# full_shift_register.net
KiCad netlist of a schematic drawn in EAGLE
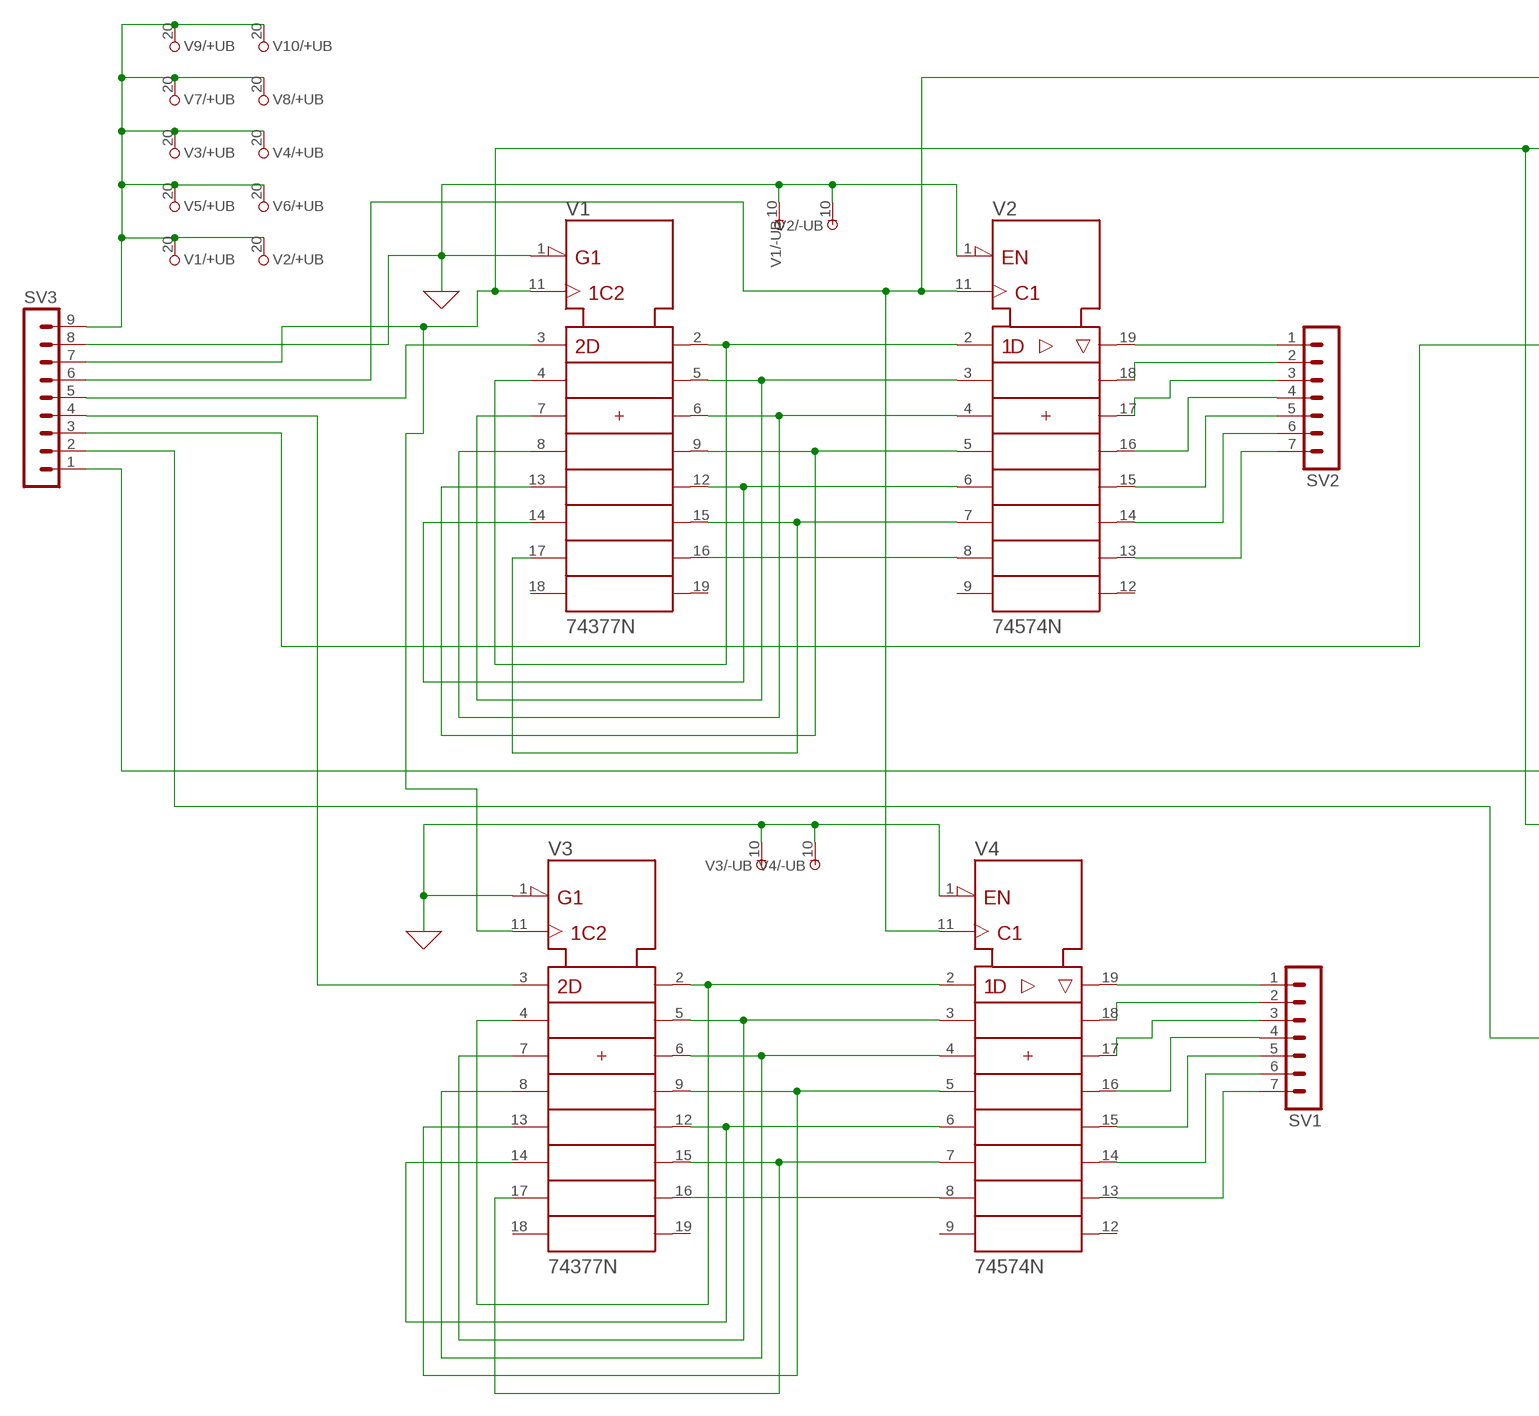
[diagram p0: schematic, sheet 1, part 1 of 2]
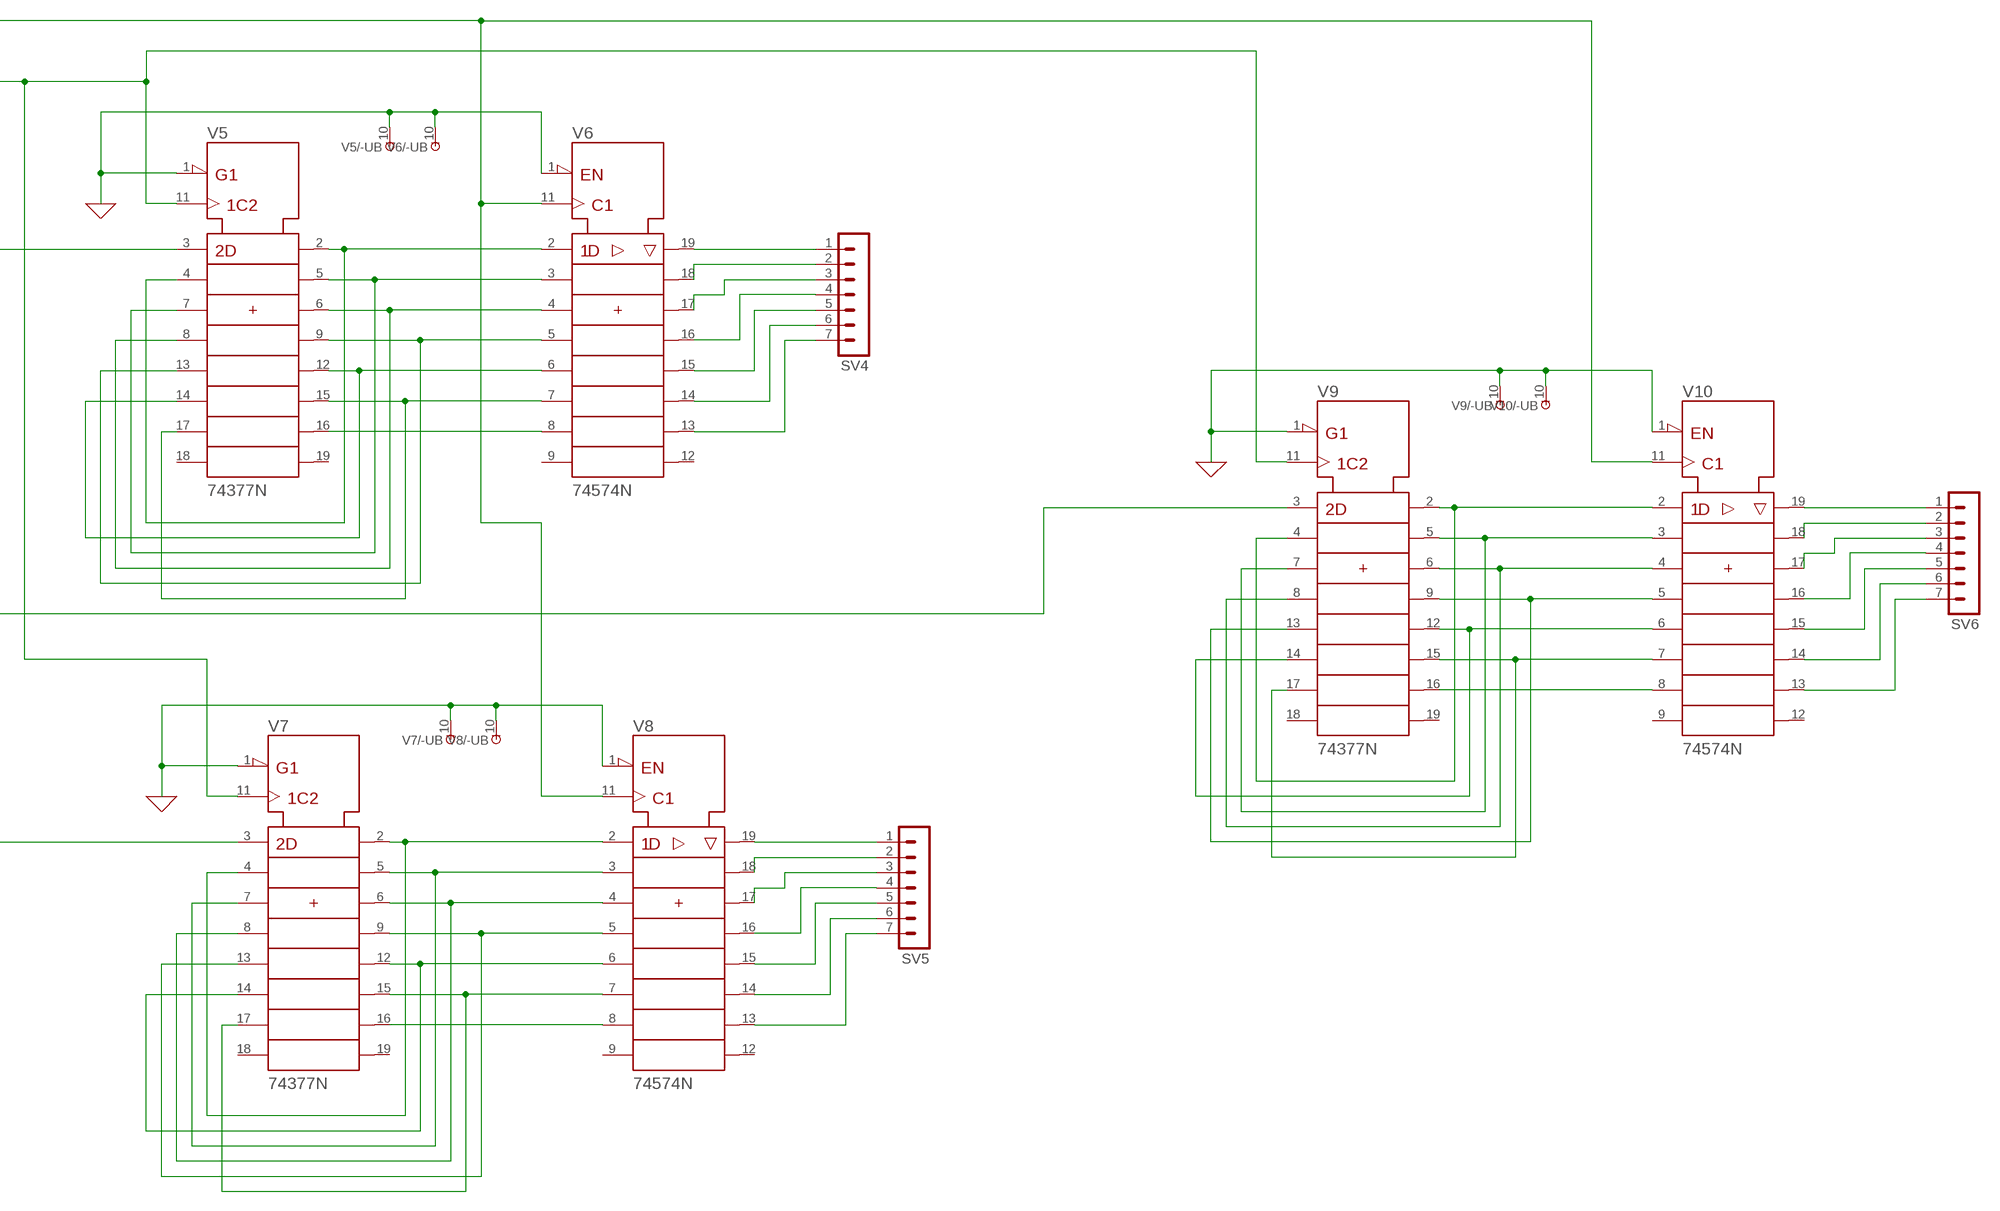
[diagram p1: schematic, sheet 1, part 2 of 2]

(export (version "E")
  (design (tool "Eeschema 10.0.6"))
  (components
    (comp (ref "SV1")
      (value "MA07-1")
      (footprint "eagle-import:MA07-1")
      (libsource (lib "eagle-import") (part "MA07-1"))
    )
    (comp (ref "SV2")
      (value "MA07-1")
      (footprint "eagle-import:MA07-1")
      (libsource (lib "eagle-import") (part "MA07-1"))
    )
    (comp (ref "SV3")
      (value "MA09-1")
      (footprint "eagle-import:MA09-1")
      (libsource (lib "eagle-import") (part "MA09-1"))
    )
    (comp (ref "SV4")
      (value "MA07-1")
      (footprint "eagle-import:MA07-1")
      (libsource (lib "eagle-import") (part "MA07-1"))
    )
    (comp (ref "SV5")
      (value "MA07-1")
      (footprint "eagle-import:MA07-1")
      (libsource (lib "eagle-import") (part "MA07-1"))
    )
    (comp (ref "SV6")
      (value "MA07-1")
      (footprint "eagle-import:MA07-1")
      (libsource (lib "eagle-import") (part "MA07-1"))
    )
    (comp (ref "V1")
      (value "74377N")
      (footprint "eagle-import:DIL20")
      (libsource (lib "eagle-import") (part "74377N"))
    )
    (comp (ref "V2")
      (value "74574N")
      (footprint "eagle-import:DIL20")
      (libsource (lib "eagle-import") (part "74574N"))
    )
    (comp (ref "V3")
      (value "74377N")
      (footprint "eagle-import:DIL20")
      (libsource (lib "eagle-import") (part "74377N"))
    )
    (comp (ref "V4")
      (value "74574N")
      (footprint "eagle-import:DIL20")
      (libsource (lib "eagle-import") (part "74574N"))
    )
    (comp (ref "V5")
      (value "74377N")
      (footprint "eagle-import:DIL20")
      (libsource (lib "eagle-import") (part "74377N"))
    )
    (comp (ref "V6")
      (value "74574N")
      (footprint "eagle-import:DIL20")
      (libsource (lib "eagle-import") (part "74574N"))
    )
    (comp (ref "V7")
      (value "74377N")
      (footprint "eagle-import:DIL20")
      (libsource (lib "eagle-import") (part "74377N"))
    )
    (comp (ref "V8")
      (value "74574N")
      (footprint "eagle-import:DIL20")
      (libsource (lib "eagle-import") (part "74574N"))
    )
    (comp (ref "V9")
      (value "74377N")
      (footprint "eagle-import:DIL20")
      (libsource (lib "eagle-import") (part "74377N"))
    )
    (comp (ref "V10")
      (value "74574N")
      (footprint "eagle-import:DIL20")
      (libsource (lib "eagle-import") (part "74574N"))
    )
  )
  (nets
    (net (code "1") (name "GND") (class "Default")
      (node (ref "SV3") (pin "8") (pinfunction "8_8") (pintype "passive"))
      (node (ref "V1") (pin "1") (pinfunction "~{G}_1") (pintype "input"))
      (node (ref "V1") (pin "10") (pinfunction "-UB_10") (pintype "power_in"))
      (node (ref "V10") (pin "1") (pinfunction "~{OC}_1") (pintype "input"))
      (node (ref "V10") (pin "10") (pinfunction "-UB_10") (pintype "power_in"))
      (node (ref "V2") (pin "1") (pinfunction "~{OC}_1") (pintype "input"))
      (node (ref "V2") (pin "10") (pinfunction "-UB_10") (pintype "power_in"))
      (node (ref "V3") (pin "1") (pinfunction "~{G}_1") (pintype "input"))
      (node (ref "V3") (pin "10") (pinfunction "-UB_10") (pintype "power_in"))
      (node (ref "V4") (pin "1") (pinfunction "~{OC}_1") (pintype "input"))
      (node (ref "V4") (pin "10") (pinfunction "-UB_10") (pintype "power_in"))
      (node (ref "V5") (pin "1") (pinfunction "~{G}_1") (pintype "input"))
      (node (ref "V5") (pin "10") (pinfunction "-UB_10") (pintype "power_in"))
      (node (ref "V6") (pin "1") (pinfunction "~{OC}_1") (pintype "input"))
      (node (ref "V6") (pin "10") (pinfunction "-UB_10") (pintype "power_in"))
      (node (ref "V7") (pin "1") (pinfunction "~{G}_1") (pintype "input"))
      (node (ref "V7") (pin "10") (pinfunction "-UB_10") (pintype "power_in"))
      (node (ref "V8") (pin "1") (pinfunction "~{OC}_1") (pintype "input"))
      (node (ref "V8") (pin "10") (pinfunction "-UB_10") (pintype "power_in"))
      (node (ref "V9") (pin "1") (pinfunction "~{G}_1") (pintype "input"))
      (node (ref "V9") (pin "10") (pinfunction "-UB_10") (pintype "power_in"))
    )
    (net (code "2") (name "Net-(V1C-1D)") (class "Default")
      (node (ref "SV3") (pin "5") (pinfunction "5_5") (pintype "passive"))
      (node (ref "V1") (pin "3") (pinfunction "1D_3") (pintype "input"))
    )
    (net (code "3") (name "Net-(V1C-1Q)") (class "Default")
      (node (ref "V1") (pin "2") (pinfunction "1Q_2") (pintype "output"))
      (node (ref "V1") (pin "4") (pinfunction "2D_4") (pintype "input"))
      (node (ref "V2") (pin "2") (pinfunction "1D_2") (pintype "input"))
    )
    (net (code "4") (name "Net-(V1C-2Q)") (class "Default")
      (node (ref "V1") (pin "5") (pinfunction "2Q_5") (pintype "output"))
      (node (ref "V1") (pin "7") (pinfunction "3D_7") (pintype "input"))
      (node (ref "V2") (pin "3") (pinfunction "2D_3") (pintype "input"))
    )
    (net (code "5") (name "Net-(V1C-3Q)") (class "Default")
      (node (ref "V1") (pin "6") (pinfunction "3Q_6") (pintype "output"))
      (node (ref "V1") (pin "8") (pinfunction "4D_8") (pintype "input"))
      (node (ref "V2") (pin "4") (pinfunction "3D_4") (pintype "input"))
    )
    (net (code "6") (name "Net-(V1C-4Q)") (class "Default")
      (node (ref "V1") (pin "13") (pinfunction "5D_13") (pintype "input"))
      (node (ref "V1") (pin "9") (pinfunction "4Q_9") (pintype "output"))
      (node (ref "V2") (pin "5") (pinfunction "4D_5") (pintype "input"))
    )
    (net (code "7") (name "Net-(V1C-5Q)") (class "Default")
      (node (ref "V1") (pin "12") (pinfunction "5Q_12") (pintype "output"))
      (node (ref "V1") (pin "14") (pinfunction "6D_14") (pintype "input"))
      (node (ref "V2") (pin "6") (pinfunction "5D_6") (pintype "input"))
    )
    (net (code "8") (name "Net-(V1C-6Q)") (class "Default")
      (node (ref "V1") (pin "15") (pinfunction "6Q_15") (pintype "output"))
      (node (ref "V1") (pin "17") (pinfunction "7D_17") (pintype "input"))
      (node (ref "V2") (pin "7") (pinfunction "6D_7") (pintype "input"))
    )
    (net (code "9") (name "Net-(V1C-7Q)") (class "Default")
      (node (ref "V1") (pin "16") (pinfunction "7Q_16") (pintype "output"))
      (node (ref "V2") (pin "8") (pinfunction "7D_8") (pintype "input"))
    )
    (net (code "10") (name "Net-(V1C-CLK)") (class "Default")
      (node (ref "SV3") (pin "7") (pinfunction "7_7") (pintype "passive"))
      (node (ref "V1") (pin "11") (pinfunction "CLK_11") (pintype "input"))
      (node (ref "V3") (pin "11") (pinfunction "CLK_11") (pintype "input"))
      (node (ref "V5") (pin "11") (pinfunction "CLK_11") (pintype "input"))
      (node (ref "V7") (pin "11") (pinfunction "CLK_11") (pintype "input"))
      (node (ref "V9") (pin "11") (pinfunction "CLK_11") (pintype "input"))
    )
    (net (code "11") (name "Net-(V2C-1Q)") (class "Default")
      (node (ref "SV2") (pin "1") (pinfunction "1_1") (pintype "passive"))
      (node (ref "V2") (pin "19") (pinfunction "1Q_19") (pintype "tri_state"))
    )
    (net (code "12") (name "Net-(V2C-2Q)") (class "Default")
      (node (ref "SV2") (pin "2") (pinfunction "2_2") (pintype "passive"))
      (node (ref "V2") (pin "18") (pinfunction "2Q_18") (pintype "tri_state"))
    )
    (net (code "13") (name "Net-(V2C-3Q)") (class "Default")
      (node (ref "SV2") (pin "3") (pinfunction "3_3") (pintype "passive"))
      (node (ref "V2") (pin "17") (pinfunction "3Q_17") (pintype "tri_state"))
    )
    (net (code "14") (name "Net-(V2C-4Q)") (class "Default")
      (node (ref "SV2") (pin "4") (pinfunction "4_4") (pintype "passive"))
      (node (ref "V2") (pin "16") (pinfunction "4Q_16") (pintype "tri_state"))
    )
    (net (code "15") (name "Net-(V2C-5Q)") (class "Default")
      (node (ref "SV2") (pin "5") (pinfunction "5_5") (pintype "passive"))
      (node (ref "V2") (pin "15") (pinfunction "5Q_15") (pintype "tri_state"))
    )
    (net (code "16") (name "Net-(V2C-6Q)") (class "Default")
      (node (ref "SV2") (pin "6") (pinfunction "6_6") (pintype "passive"))
      (node (ref "V2") (pin "14") (pinfunction "6Q_14") (pintype "tri_state"))
    )
    (net (code "17") (name "Net-(V2C-7Q)") (class "Default")
      (node (ref "SV2") (pin "7") (pinfunction "7_7") (pintype "passive"))
      (node (ref "V2") (pin "13") (pinfunction "7Q_13") (pintype "tri_state"))
    )
    (net (code "18") (name "Net-(V3C-1D)") (class "Default")
      (node (ref "SV3") (pin "4") (pinfunction "4_4") (pintype "passive"))
      (node (ref "V3") (pin "3") (pinfunction "1D_3") (pintype "input"))
    )
    (net (code "19") (name "Net-(V3C-1Q)") (class "Default")
      (node (ref "V3") (pin "2") (pinfunction "1Q_2") (pintype "output"))
      (node (ref "V3") (pin "4") (pinfunction "2D_4") (pintype "input"))
      (node (ref "V4") (pin "2") (pinfunction "1D_2") (pintype "input"))
    )
    (net (code "20") (name "Net-(V3C-2Q)") (class "Default")
      (node (ref "V3") (pin "5") (pinfunction "2Q_5") (pintype "output"))
      (node (ref "V3") (pin "7") (pinfunction "3D_7") (pintype "input"))
      (node (ref "V4") (pin "3") (pinfunction "2D_3") (pintype "input"))
    )
    (net (code "21") (name "Net-(V3C-3Q)") (class "Default")
      (node (ref "V3") (pin "6") (pinfunction "3Q_6") (pintype "output"))
      (node (ref "V3") (pin "8") (pinfunction "4D_8") (pintype "input"))
      (node (ref "V4") (pin "4") (pinfunction "3D_4") (pintype "input"))
    )
    (net (code "22") (name "Net-(V3C-4Q)") (class "Default")
      (node (ref "V3") (pin "13") (pinfunction "5D_13") (pintype "input"))
      (node (ref "V3") (pin "9") (pinfunction "4Q_9") (pintype "output"))
      (node (ref "V4") (pin "5") (pinfunction "4D_5") (pintype "input"))
    )
    (net (code "23") (name "Net-(V3C-5Q)") (class "Default")
      (node (ref "V3") (pin "12") (pinfunction "5Q_12") (pintype "output"))
      (node (ref "V3") (pin "14") (pinfunction "6D_14") (pintype "input"))
      (node (ref "V4") (pin "6") (pinfunction "5D_6") (pintype "input"))
    )
    (net (code "24") (name "Net-(V3C-6Q)") (class "Default")
      (node (ref "V3") (pin "15") (pinfunction "6Q_15") (pintype "output"))
      (node (ref "V3") (pin "17") (pinfunction "7D_17") (pintype "input"))
      (node (ref "V4") (pin "7") (pinfunction "6D_7") (pintype "input"))
    )
    (net (code "25") (name "Net-(V3C-7Q)") (class "Default")
      (node (ref "V3") (pin "16") (pinfunction "7Q_16") (pintype "output"))
      (node (ref "V4") (pin "8") (pinfunction "7D_8") (pintype "input"))
    )
    (net (code "26") (name "Net-(V4C-1Q)") (class "Default")
      (node (ref "SV1") (pin "1") (pinfunction "1_1") (pintype "passive"))
      (node (ref "V4") (pin "19") (pinfunction "1Q_19") (pintype "tri_state"))
    )
    (net (code "27") (name "Net-(V4C-2Q)") (class "Default")
      (node (ref "SV1") (pin "2") (pinfunction "2_2") (pintype "passive"))
      (node (ref "V4") (pin "18") (pinfunction "2Q_18") (pintype "tri_state"))
    )
    (net (code "28") (name "Net-(V4C-3Q)") (class "Default")
      (node (ref "SV1") (pin "3") (pinfunction "3_3") (pintype "passive"))
      (node (ref "V4") (pin "17") (pinfunction "3Q_17") (pintype "tri_state"))
    )
    (net (code "29") (name "Net-(V4C-4Q)") (class "Default")
      (node (ref "SV1") (pin "4") (pinfunction "4_4") (pintype "passive"))
      (node (ref "V4") (pin "16") (pinfunction "4Q_16") (pintype "tri_state"))
    )
    (net (code "30") (name "Net-(V4C-5Q)") (class "Default")
      (node (ref "SV1") (pin "5") (pinfunction "5_5") (pintype "passive"))
      (node (ref "V4") (pin "15") (pinfunction "5Q_15") (pintype "tri_state"))
    )
    (net (code "31") (name "Net-(V4C-6Q)") (class "Default")
      (node (ref "SV1") (pin "6") (pinfunction "6_6") (pintype "passive"))
      (node (ref "V4") (pin "14") (pinfunction "6Q_14") (pintype "tri_state"))
    )
    (net (code "32") (name "Net-(V4C-7Q)") (class "Default")
      (node (ref "SV1") (pin "7") (pinfunction "7_7") (pintype "passive"))
      (node (ref "V4") (pin "13") (pinfunction "7Q_13") (pintype "tri_state"))
    )
    (net (code "33") (name "Net-(V5C-1D)") (class "Default")
      (node (ref "SV3") (pin "3") (pinfunction "3_3") (pintype "passive"))
      (node (ref "V5") (pin "3") (pinfunction "1D_3") (pintype "input"))
    )
    (net (code "34") (name "Net-(V5C-1Q)") (class "Default")
      (node (ref "V5") (pin "2") (pinfunction "1Q_2") (pintype "output"))
      (node (ref "V5") (pin "4") (pinfunction "2D_4") (pintype "input"))
      (node (ref "V6") (pin "2") (pinfunction "1D_2") (pintype "input"))
    )
    (net (code "35") (name "Net-(V5C-2Q)") (class "Default")
      (node (ref "V5") (pin "5") (pinfunction "2Q_5") (pintype "output"))
      (node (ref "V5") (pin "7") (pinfunction "3D_7") (pintype "input"))
      (node (ref "V6") (pin "3") (pinfunction "2D_3") (pintype "input"))
    )
    (net (code "36") (name "Net-(V5C-3Q)") (class "Default")
      (node (ref "V5") (pin "6") (pinfunction "3Q_6") (pintype "output"))
      (node (ref "V5") (pin "8") (pinfunction "4D_8") (pintype "input"))
      (node (ref "V6") (pin "4") (pinfunction "3D_4") (pintype "input"))
    )
    (net (code "37") (name "Net-(V5C-4Q)") (class "Default")
      (node (ref "V5") (pin "13") (pinfunction "5D_13") (pintype "input"))
      (node (ref "V5") (pin "9") (pinfunction "4Q_9") (pintype "output"))
      (node (ref "V6") (pin "5") (pinfunction "4D_5") (pintype "input"))
    )
    (net (code "38") (name "Net-(V5C-5Q)") (class "Default")
      (node (ref "V5") (pin "12") (pinfunction "5Q_12") (pintype "output"))
      (node (ref "V5") (pin "14") (pinfunction "6D_14") (pintype "input"))
      (node (ref "V6") (pin "6") (pinfunction "5D_6") (pintype "input"))
    )
    (net (code "39") (name "Net-(V5C-6Q)") (class "Default")
      (node (ref "V5") (pin "15") (pinfunction "6Q_15") (pintype "output"))
      (node (ref "V5") (pin "17") (pinfunction "7D_17") (pintype "input"))
      (node (ref "V6") (pin "7") (pinfunction "6D_7") (pintype "input"))
    )
    (net (code "40") (name "Net-(V5C-7Q)") (class "Default")
      (node (ref "V5") (pin "16") (pinfunction "7Q_16") (pintype "output"))
      (node (ref "V6") (pin "8") (pinfunction "7D_8") (pintype "input"))
    )
    (net (code "41") (name "Net-(V6C-1Q)") (class "Default")
      (node (ref "SV4") (pin "1") (pinfunction "1_1") (pintype "passive"))
      (node (ref "V6") (pin "19") (pinfunction "1Q_19") (pintype "tri_state"))
    )
    (net (code "42") (name "Net-(V6C-2Q)") (class "Default")
      (node (ref "SV4") (pin "2") (pinfunction "2_2") (pintype "passive"))
      (node (ref "V6") (pin "18") (pinfunction "2Q_18") (pintype "tri_state"))
    )
    (net (code "43") (name "Net-(V6C-3Q)") (class "Default")
      (node (ref "SV4") (pin "3") (pinfunction "3_3") (pintype "passive"))
      (node (ref "V6") (pin "17") (pinfunction "3Q_17") (pintype "tri_state"))
    )
    (net (code "44") (name "Net-(V6C-4Q)") (class "Default")
      (node (ref "SV4") (pin "4") (pinfunction "4_4") (pintype "passive"))
      (node (ref "V6") (pin "16") (pinfunction "4Q_16") (pintype "tri_state"))
    )
    (net (code "45") (name "Net-(V6C-5Q)") (class "Default")
      (node (ref "SV4") (pin "5") (pinfunction "5_5") (pintype "passive"))
      (node (ref "V6") (pin "15") (pinfunction "5Q_15") (pintype "tri_state"))
    )
    (net (code "46") (name "Net-(V6C-6Q)") (class "Default")
      (node (ref "SV4") (pin "6") (pinfunction "6_6") (pintype "passive"))
      (node (ref "V6") (pin "14") (pinfunction "6Q_14") (pintype "tri_state"))
    )
    (net (code "47") (name "Net-(V6C-7Q)") (class "Default")
      (node (ref "SV4") (pin "7") (pinfunction "7_7") (pintype "passive"))
      (node (ref "V6") (pin "13") (pinfunction "7Q_13") (pintype "tri_state"))
    )
    (net (code "48") (name "Net-(V7C-1D)") (class "Default")
      (node (ref "SV3") (pin "2") (pinfunction "2_2") (pintype "passive"))
      (node (ref "V7") (pin "3") (pinfunction "1D_3") (pintype "input"))
    )
    (net (code "49") (name "Net-(V7C-1Q)") (class "Default")
      (node (ref "V7") (pin "2") (pinfunction "1Q_2") (pintype "output"))
      (node (ref "V7") (pin "4") (pinfunction "2D_4") (pintype "input"))
      (node (ref "V8") (pin "2") (pinfunction "1D_2") (pintype "input"))
    )
    (net (code "50") (name "Net-(V7C-2Q)") (class "Default")
      (node (ref "V7") (pin "5") (pinfunction "2Q_5") (pintype "output"))
      (node (ref "V7") (pin "7") (pinfunction "3D_7") (pintype "input"))
      (node (ref "V8") (pin "3") (pinfunction "2D_3") (pintype "input"))
    )
    (net (code "51") (name "Net-(V7C-3Q)") (class "Default")
      (node (ref "V7") (pin "6") (pinfunction "3Q_6") (pintype "output"))
      (node (ref "V7") (pin "8") (pinfunction "4D_8") (pintype "input"))
      (node (ref "V8") (pin "4") (pinfunction "3D_4") (pintype "input"))
    )
    (net (code "52") (name "Net-(V7C-4Q)") (class "Default")
      (node (ref "V7") (pin "13") (pinfunction "5D_13") (pintype "input"))
      (node (ref "V7") (pin "9") (pinfunction "4Q_9") (pintype "output"))
      (node (ref "V8") (pin "5") (pinfunction "4D_5") (pintype "input"))
    )
    (net (code "53") (name "Net-(V7C-5Q)") (class "Default")
      (node (ref "V7") (pin "12") (pinfunction "5Q_12") (pintype "output"))
      (node (ref "V7") (pin "14") (pinfunction "6D_14") (pintype "input"))
      (node (ref "V8") (pin "6") (pinfunction "5D_6") (pintype "input"))
    )
    (net (code "54") (name "Net-(V7C-6Q)") (class "Default")
      (node (ref "V7") (pin "15") (pinfunction "6Q_15") (pintype "output"))
      (node (ref "V7") (pin "17") (pinfunction "7D_17") (pintype "input"))
      (node (ref "V8") (pin "7") (pinfunction "6D_7") (pintype "input"))
    )
    (net (code "55") (name "Net-(V7C-7Q)") (class "Default")
      (node (ref "V7") (pin "16") (pinfunction "7Q_16") (pintype "output"))
      (node (ref "V8") (pin "8") (pinfunction "7D_8") (pintype "input"))
    )
    (net (code "56") (name "Net-(V8C-1Q)") (class "Default")
      (node (ref "SV5") (pin "1") (pinfunction "1_1") (pintype "passive"))
      (node (ref "V8") (pin "19") (pinfunction "1Q_19") (pintype "tri_state"))
    )
    (net (code "57") (name "Net-(V8C-2Q)") (class "Default")
      (node (ref "SV5") (pin "2") (pinfunction "2_2") (pintype "passive"))
      (node (ref "V8") (pin "18") (pinfunction "2Q_18") (pintype "tri_state"))
    )
    (net (code "58") (name "Net-(V8C-3Q)") (class "Default")
      (node (ref "SV5") (pin "3") (pinfunction "3_3") (pintype "passive"))
      (node (ref "V8") (pin "17") (pinfunction "3Q_17") (pintype "tri_state"))
    )
    (net (code "59") (name "Net-(V8C-4Q)") (class "Default")
      (node (ref "SV5") (pin "4") (pinfunction "4_4") (pintype "passive"))
      (node (ref "V8") (pin "16") (pinfunction "4Q_16") (pintype "tri_state"))
    )
    (net (code "60") (name "Net-(V8C-5Q)") (class "Default")
      (node (ref "SV5") (pin "5") (pinfunction "5_5") (pintype "passive"))
      (node (ref "V8") (pin "15") (pinfunction "5Q_15") (pintype "tri_state"))
    )
    (net (code "61") (name "Net-(V8C-6Q)") (class "Default")
      (node (ref "SV5") (pin "6") (pinfunction "6_6") (pintype "passive"))
      (node (ref "V8") (pin "14") (pinfunction "6Q_14") (pintype "tri_state"))
    )
    (net (code "62") (name "Net-(V8C-7Q)") (class "Default")
      (node (ref "SV5") (pin "7") (pinfunction "7_7") (pintype "passive"))
      (node (ref "V8") (pin "13") (pinfunction "7Q_13") (pintype "tri_state"))
    )
    (net (code "63") (name "Net-(V9C-1D)") (class "Default")
      (node (ref "SV3") (pin "1") (pinfunction "1_1") (pintype "passive"))
      (node (ref "V9") (pin "3") (pinfunction "1D_3") (pintype "input"))
    )
    (net (code "64") (name "Net-(V10A-+UB)") (class "Default")
      (node (ref "SV3") (pin "9") (pinfunction "9_9") (pintype "passive"))
      (node (ref "V1") (pin "20") (pinfunction "+UB_20") (pintype "power_in"))
      (node (ref "V10") (pin "20") (pinfunction "+UB_20") (pintype "power_in"))
      (node (ref "V2") (pin "20") (pinfunction "+UB_20") (pintype "power_in"))
      (node (ref "V3") (pin "20") (pinfunction "+UB_20") (pintype "power_in"))
      (node (ref "V4") (pin "20") (pinfunction "+UB_20") (pintype "power_in"))
      (node (ref "V5") (pin "20") (pinfunction "+UB_20") (pintype "power_in"))
      (node (ref "V6") (pin "20") (pinfunction "+UB_20") (pintype "power_in"))
      (node (ref "V7") (pin "20") (pinfunction "+UB_20") (pintype "power_in"))
      (node (ref "V8") (pin "20") (pinfunction "+UB_20") (pintype "power_in"))
      (node (ref "V9") (pin "20") (pinfunction "+UB_20") (pintype "power_in"))
    )
    (net (code "65") (name "Net-(V10C-1D)") (class "Default")
      (node (ref "V10") (pin "2") (pinfunction "1D_2") (pintype "input"))
      (node (ref "V9") (pin "2") (pinfunction "1Q_2") (pintype "output"))
      (node (ref "V9") (pin "4") (pinfunction "2D_4") (pintype "input"))
    )
    (net (code "66") (name "Net-(V10C-1Q)") (class "Default")
      (node (ref "SV6") (pin "1") (pinfunction "1_1") (pintype "passive"))
      (node (ref "V10") (pin "19") (pinfunction "1Q_19") (pintype "tri_state"))
    )
    (net (code "67") (name "Net-(V10C-2D)") (class "Default")
      (node (ref "V10") (pin "3") (pinfunction "2D_3") (pintype "input"))
      (node (ref "V9") (pin "5") (pinfunction "2Q_5") (pintype "output"))
      (node (ref "V9") (pin "7") (pinfunction "3D_7") (pintype "input"))
    )
    (net (code "68") (name "Net-(V10C-2Q)") (class "Default")
      (node (ref "SV6") (pin "2") (pinfunction "2_2") (pintype "passive"))
      (node (ref "V10") (pin "18") (pinfunction "2Q_18") (pintype "tri_state"))
    )
    (net (code "69") (name "Net-(V10C-3D)") (class "Default")
      (node (ref "V10") (pin "4") (pinfunction "3D_4") (pintype "input"))
      (node (ref "V9") (pin "6") (pinfunction "3Q_6") (pintype "output"))
      (node (ref "V9") (pin "8") (pinfunction "4D_8") (pintype "input"))
    )
    (net (code "70") (name "Net-(V10C-3Q)") (class "Default")
      (node (ref "SV6") (pin "3") (pinfunction "3_3") (pintype "passive"))
      (node (ref "V10") (pin "17") (pinfunction "3Q_17") (pintype "tri_state"))
    )
    (net (code "71") (name "Net-(V10C-4D)") (class "Default")
      (node (ref "V10") (pin "5") (pinfunction "4D_5") (pintype "input"))
      (node (ref "V9") (pin "13") (pinfunction "5D_13") (pintype "input"))
      (node (ref "V9") (pin "9") (pinfunction "4Q_9") (pintype "output"))
    )
    (net (code "72") (name "Net-(V10C-4Q)") (class "Default")
      (node (ref "SV6") (pin "4") (pinfunction "4_4") (pintype "passive"))
      (node (ref "V10") (pin "16") (pinfunction "4Q_16") (pintype "tri_state"))
    )
    (net (code "73") (name "Net-(V10C-5D)") (class "Default")
      (node (ref "V10") (pin "6") (pinfunction "5D_6") (pintype "input"))
      (node (ref "V9") (pin "12") (pinfunction "5Q_12") (pintype "output"))
      (node (ref "V9") (pin "14") (pinfunction "6D_14") (pintype "input"))
    )
    (net (code "74") (name "Net-(V10C-5Q)") (class "Default")
      (node (ref "SV6") (pin "5") (pinfunction "5_5") (pintype "passive"))
      (node (ref "V10") (pin "15") (pinfunction "5Q_15") (pintype "tri_state"))
    )
    (net (code "75") (name "Net-(V10C-6D)") (class "Default")
      (node (ref "V10") (pin "7") (pinfunction "6D_7") (pintype "input"))
      (node (ref "V9") (pin "15") (pinfunction "6Q_15") (pintype "output"))
      (node (ref "V9") (pin "17") (pinfunction "7D_17") (pintype "input"))
    )
    (net (code "76") (name "Net-(V10C-6Q)") (class "Default")
      (node (ref "SV6") (pin "6") (pinfunction "6_6") (pintype "passive"))
      (node (ref "V10") (pin "14") (pinfunction "6Q_14") (pintype "tri_state"))
    )
    (net (code "77") (name "Net-(V10C-7D)") (class "Default")
      (node (ref "V10") (pin "8") (pinfunction "7D_8") (pintype "input"))
      (node (ref "V9") (pin "16") (pinfunction "7Q_16") (pintype "output"))
    )
    (net (code "78") (name "Net-(V10C-7Q)") (class "Default")
      (node (ref "SV6") (pin "7") (pinfunction "7_7") (pintype "passive"))
      (node (ref "V10") (pin "13") (pinfunction "7Q_13") (pintype "tri_state"))
    )
    (net (code "79") (name "Net-(V10C-CLK)") (class "Default")
      (node (ref "SV3") (pin "6") (pinfunction "6_6") (pintype "passive"))
      (node (ref "V10") (pin "11") (pinfunction "CLK_11") (pintype "input"))
      (node (ref "V2") (pin "11") (pinfunction "CLK_11") (pintype "input"))
      (node (ref "V4") (pin "11") (pinfunction "CLK_11") (pintype "input"))
      (node (ref "V6") (pin "11") (pinfunction "CLK_11") (pintype "input"))
      (node (ref "V8") (pin "11") (pinfunction "CLK_11") (pintype "input"))
    )
    (net (code "80") (name "unconnected-(V1C-8D-Pad18)") (class "Default")
      (node (ref "V1") (pin "18") (pinfunction "8D_18") (pintype "input"))
    )
    (net (code "81") (name "unconnected-(V1C-8Q-Pad19)") (class "Default")
      (node (ref "V1") (pin "19") (pinfunction "8Q_19") (pintype "output"))
    )
    (net (code "82") (name "unconnected-(V2C-8D-Pad9)") (class "Default")
      (node (ref "V2") (pin "9") (pinfunction "8D_9") (pintype "input"))
    )
    (net (code "83") (name "unconnected-(V2C-8Q-Pad12)") (class "Default")
      (node (ref "V2") (pin "12") (pinfunction "8Q_12") (pintype "tri_state"))
    )
    (net (code "84") (name "unconnected-(V3C-8D-Pad18)") (class "Default")
      (node (ref "V3") (pin "18") (pinfunction "8D_18") (pintype "input"))
    )
    (net (code "85") (name "unconnected-(V3C-8Q-Pad19)") (class "Default")
      (node (ref "V3") (pin "19") (pinfunction "8Q_19") (pintype "output"))
    )
    (net (code "86") (name "unconnected-(V4C-8D-Pad9)") (class "Default")
      (node (ref "V4") (pin "9") (pinfunction "8D_9") (pintype "input"))
    )
    (net (code "87") (name "unconnected-(V4C-8Q-Pad12)") (class "Default")
      (node (ref "V4") (pin "12") (pinfunction "8Q_12") (pintype "tri_state"))
    )
    (net (code "88") (name "unconnected-(V5C-8D-Pad18)") (class "Default")
      (node (ref "V5") (pin "18") (pinfunction "8D_18") (pintype "input"))
    )
    (net (code "89") (name "unconnected-(V5C-8Q-Pad19)") (class "Default")
      (node (ref "V5") (pin "19") (pinfunction "8Q_19") (pintype "output"))
    )
    (net (code "90") (name "unconnected-(V6C-8D-Pad9)") (class "Default")
      (node (ref "V6") (pin "9") (pinfunction "8D_9") (pintype "input"))
    )
    (net (code "91") (name "unconnected-(V6C-8Q-Pad12)") (class "Default")
      (node (ref "V6") (pin "12") (pinfunction "8Q_12") (pintype "tri_state"))
    )
    (net (code "92") (name "unconnected-(V7C-8D-Pad18)") (class "Default")
      (node (ref "V7") (pin "18") (pinfunction "8D_18") (pintype "input"))
    )
    (net (code "93") (name "unconnected-(V7C-8Q-Pad19)") (class "Default")
      (node (ref "V7") (pin "19") (pinfunction "8Q_19") (pintype "output"))
    )
    (net (code "94") (name "unconnected-(V8C-8D-Pad9)") (class "Default")
      (node (ref "V8") (pin "9") (pinfunction "8D_9") (pintype "input"))
    )
    (net (code "95") (name "unconnected-(V8C-8Q-Pad12)") (class "Default")
      (node (ref "V8") (pin "12") (pinfunction "8Q_12") (pintype "tri_state"))
    )
    (net (code "96") (name "unconnected-(V9C-8D-Pad18)") (class "Default")
      (node (ref "V9") (pin "18") (pinfunction "8D_18") (pintype "input"))
    )
    (net (code "97") (name "unconnected-(V9C-8Q-Pad19)") (class "Default")
      (node (ref "V9") (pin "19") (pinfunction "8Q_19") (pintype "output"))
    )
    (net (code "98") (name "unconnected-(V10C-8D-Pad9)") (class "Default")
      (node (ref "V10") (pin "9") (pinfunction "8D_9") (pintype "input"))
    )
    (net (code "99") (name "unconnected-(V10C-8Q-Pad12)") (class "Default")
      (node (ref "V10") (pin "12") (pinfunction "8Q_12") (pintype "tri_state"))
    )
  )
)
